# am-1801.net
KiCad netlist of a schematic drawn in EAGLE
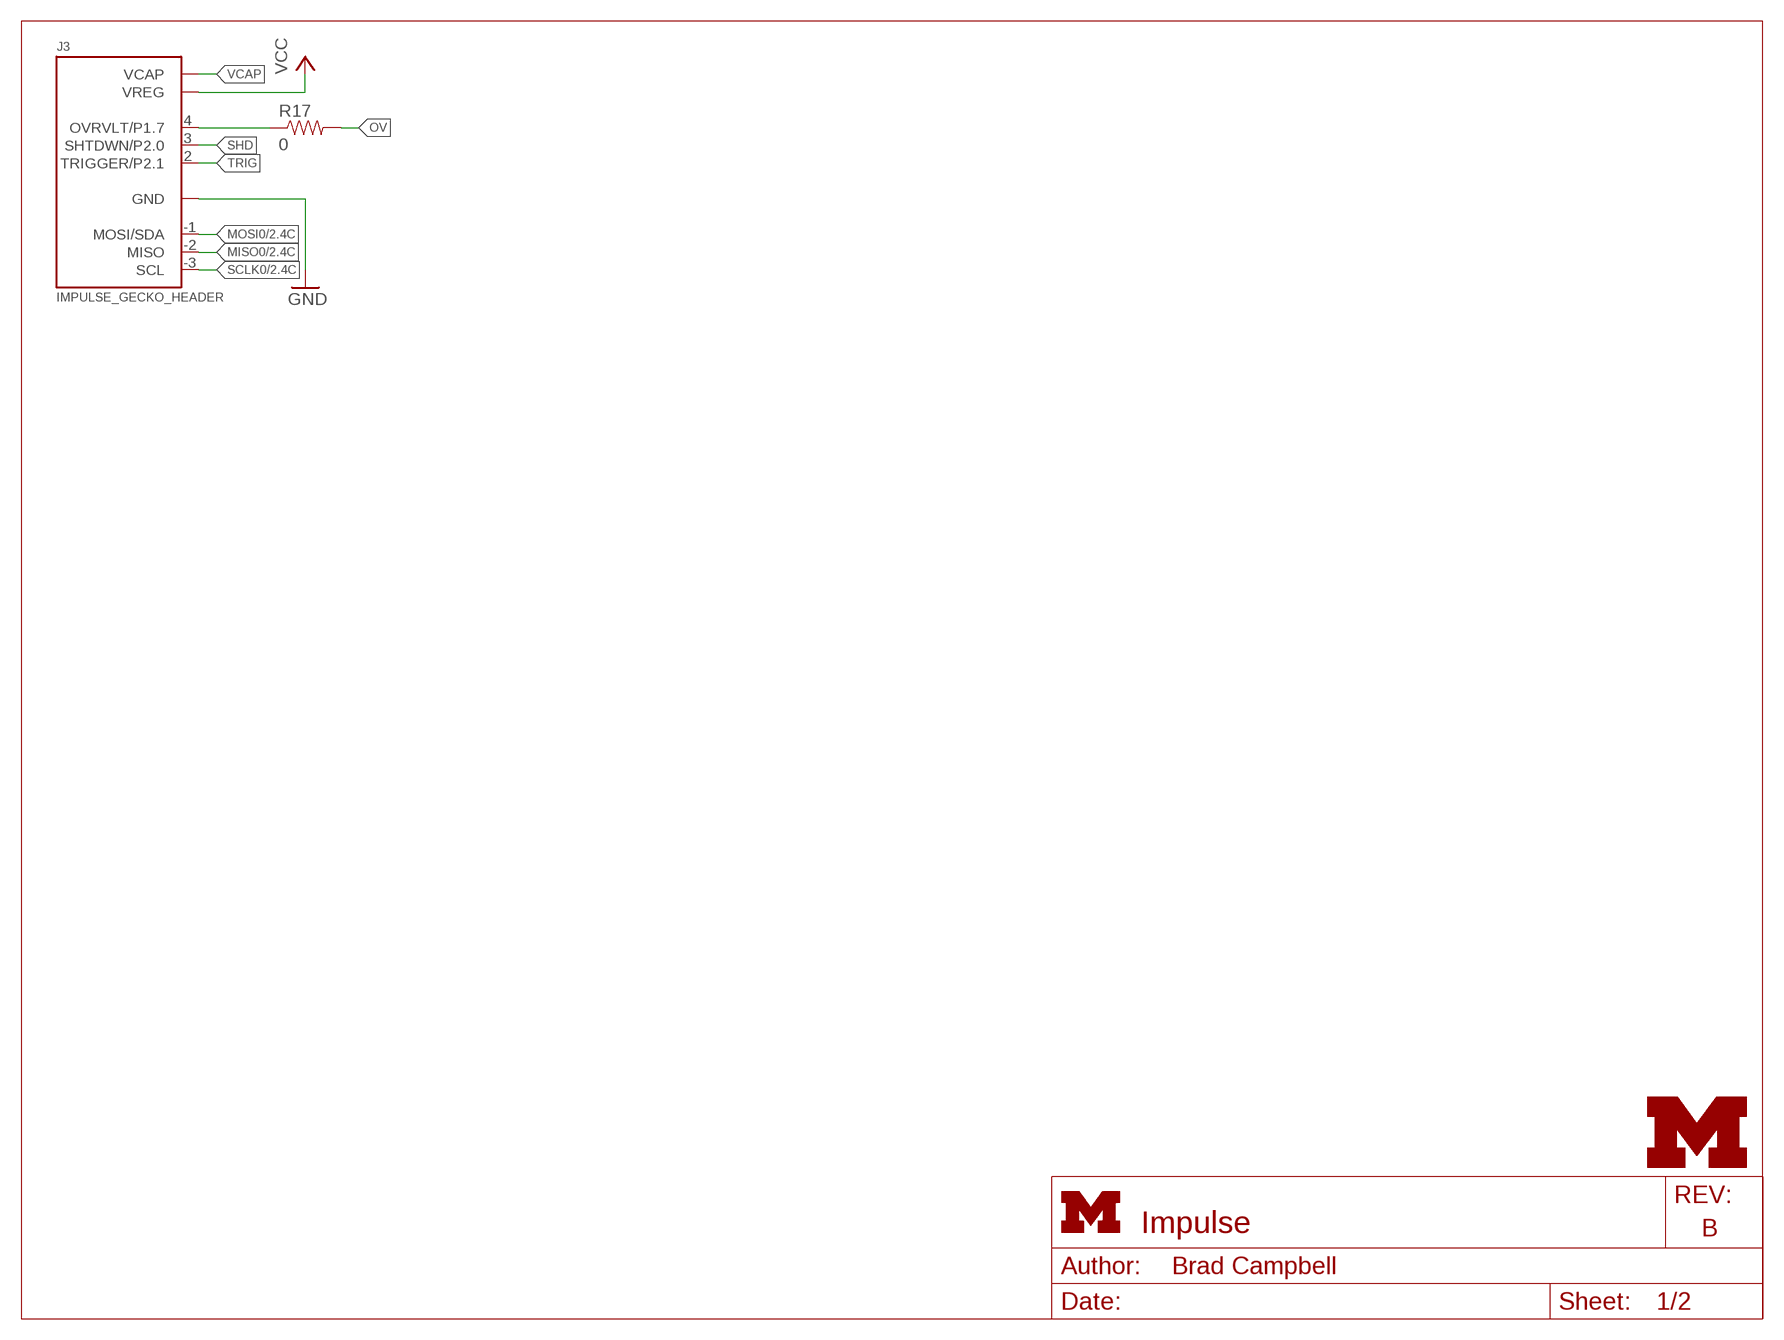
[diagram p0: schematic, sheet 1]
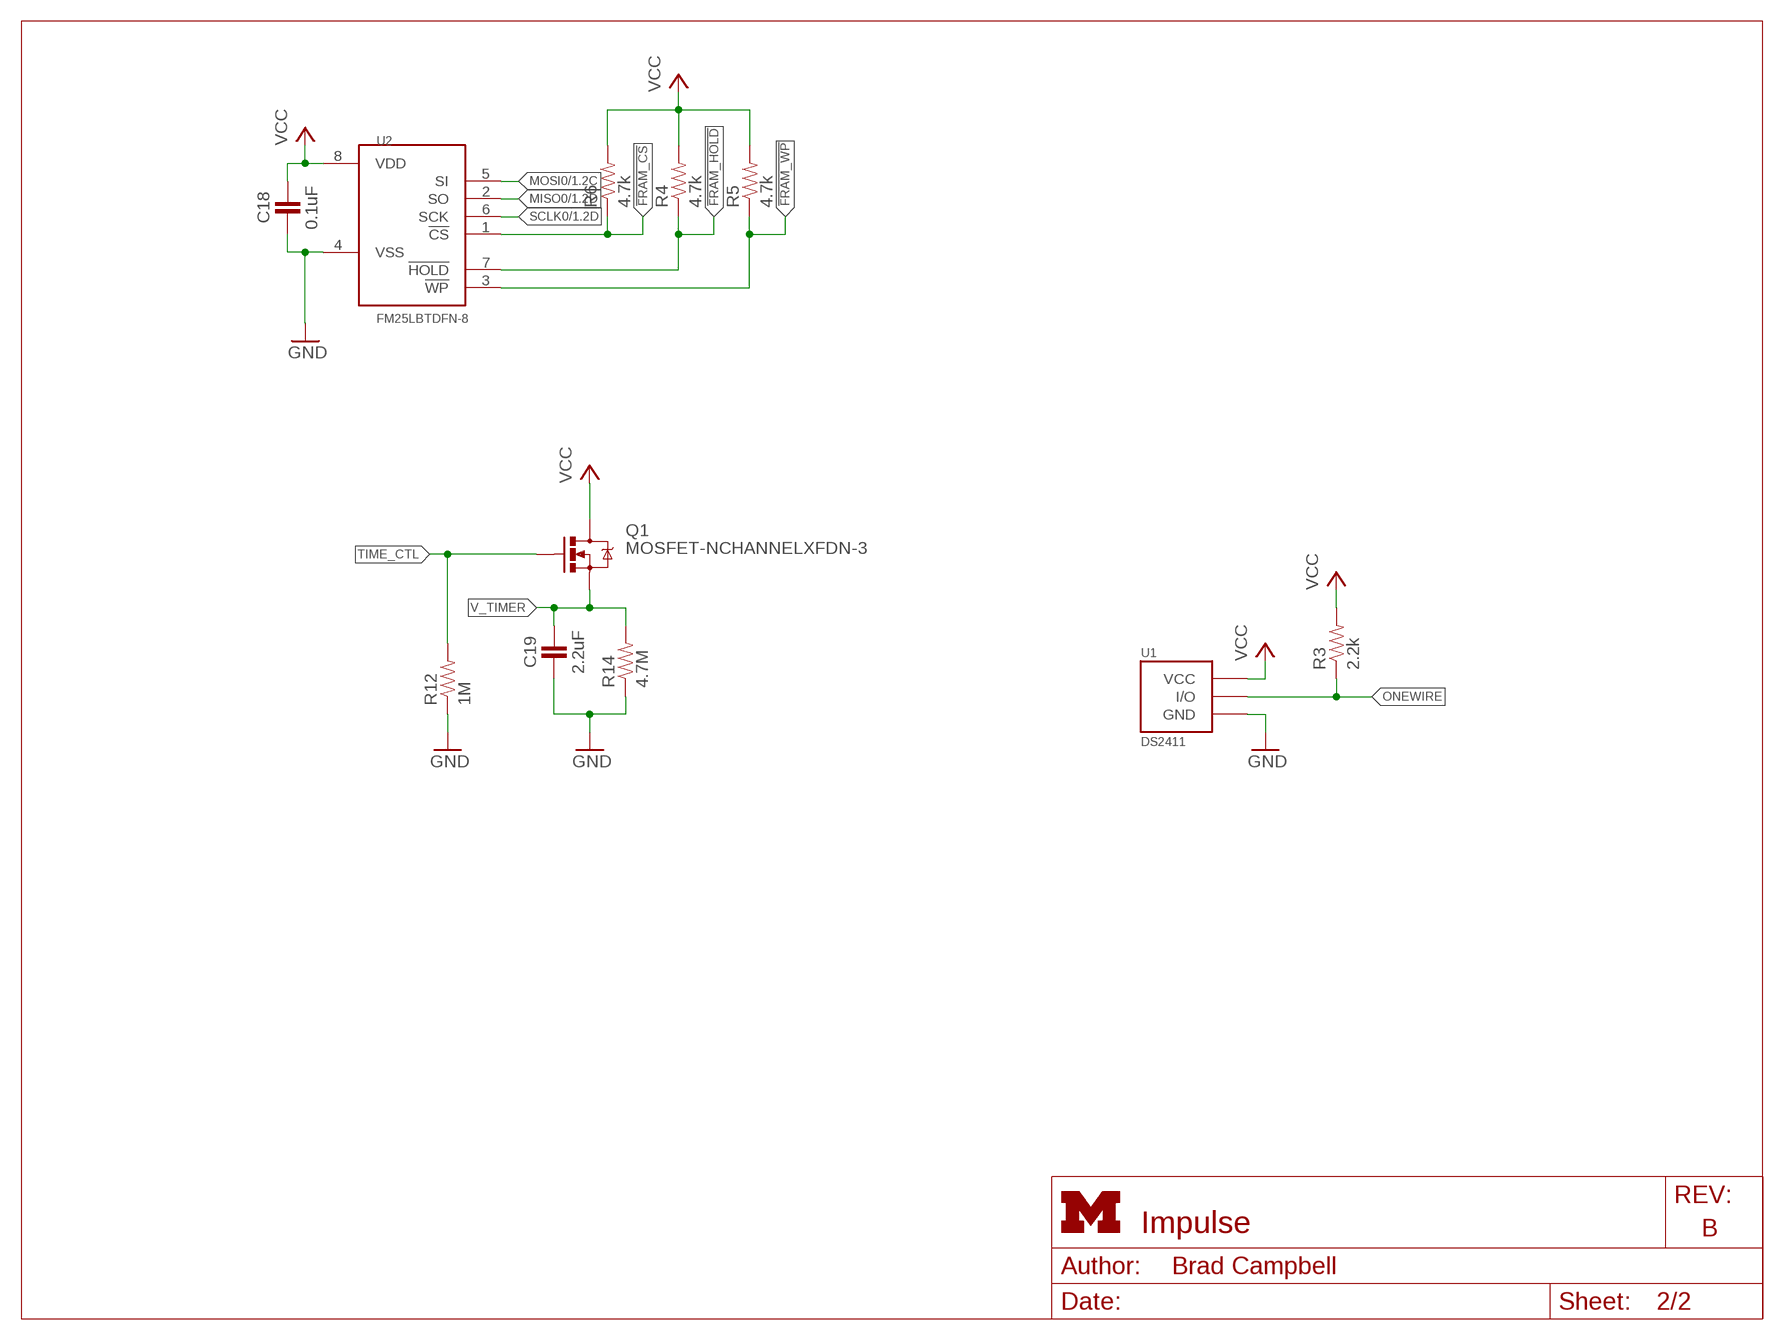
[diagram p1: schematic, sheet 2]

(export (version "E")
  (design (tool "Eeschema 10.0.6"))
  (components
    (comp (ref "C18")
      (value "0.1uF")
      (footprint "eagle-import:0402_CAP")
      (libsource (lib "eagle-import") (part "CAPACITOR"))
    )
    (comp (ref "C19")
      (value "2.2uF")
      (footprint "eagle-import:0402_CAP")
      (libsource (lib "eagle-import") (part "CAPACITOR"))
    )
    (comp (ref "Q1")
      (value "MOSFET-NCHANNELXFDN-3")
      (footprint "eagle-import:XFDFN-3")
      (libsource (lib "eagle-import") (part "MOSFET-NCHANNELXFDN-3"))
    )
    (comp (ref "R3")
      (value "2.2k")
      (footprint "eagle-import:0402_RES")
      (libsource (lib "eagle-import") (part "RESISTOR"))
    )
    (comp (ref "R4")
      (value "4.7k")
      (footprint "eagle-import:0402_RES")
      (libsource (lib "eagle-import") (part "RESISTOR"))
    )
    (comp (ref "R5")
      (value "4.7k")
      (footprint "eagle-import:0402_RES")
      (libsource (lib "eagle-import") (part "RESISTOR"))
    )
    (comp (ref "R6")
      (value "4.7k")
      (footprint "eagle-import:0402_RES")
      (libsource (lib "eagle-import") (part "RESISTOR"))
    )
    (comp (ref "R12")
      (value "1M")
      (footprint "eagle-import:0402_RES")
      (libsource (lib "eagle-import") (part "RESISTOR"))
    )
    (comp (ref "R14")
      (value "4.7M")
      (footprint "eagle-import:0402_RES")
      (libsource (lib "eagle-import") (part "RESISTOR"))
    )
    (comp (ref "U1")
      (value "DS2411")
      (footprint "eagle-import:SOT-23")
      (libsource (lib "eagle-import") (part "DS2411"))
    )
    (comp (ref "U2")
      (value "FM25LBTDFN-8")
      (footprint "eagle-import:TDFN-8")
      (libsource (lib "eagle-import") (part "FM25LBTDFN-8"))
    )
    (comp (ref "J3")
      (value "IMPULSE_GECKO_HEADER")
      (footprint "eagle-import:HEADER1X9_0.05IN")
      (libsource (lib "eagle-import") (part "IMPULSE_GECKO_HEADER"))
    )
    (comp (ref "R17")
      (value "0")
      (footprint "eagle-import:0402_RES")
      (libsource (lib "eagle-import") (part "RESISTOR"))
    )
    (comp (ref "U$1")
      (value "UMICH_SOLID_SMALL")
      (footprint "eagle-import:UMICH_SOLID_75MIL")
      (libsource (lib "eagle-import") (part "UMICH_SOLID_SMALL"))
    )
  )
  (nets
    (net (code "1") (name "GND") (class "Default")
      (node (ref "C18") (pin "2") (pinfunction "2_2") (pintype "bidirectional"))
      (node (ref "C19") (pin "2") (pinfunction "2_2") (pintype "bidirectional"))
      (node (ref "J3") (pin "0") (pinfunction "GND_0") (pintype "bidirectional"))
      (node (ref "R12") (pin "1") (pinfunction "1_1") (pintype "passive"))
      (node (ref "R14") (pin "1") (pinfunction "1_1") (pintype "passive"))
      (node (ref "U1") (pin "3") (pinfunction "GND_3") (pintype "bidirectional"))
      (node (ref "U2") (pin "4") (pinfunction "VSS_4") (pintype "bidirectional"))
    )
    (net (code "2") (name "MISO0") (class "Default")
      (node (ref "J3") (pin "-2") (pinfunction "MISO_-2") (pintype "bidirectional"))
      (node (ref "U2") (pin "2") (pinfunction "SO_2") (pintype "bidirectional"))
    )
    (net (code "3") (name "MOSI0") (class "Default")
      (node (ref "J3") (pin "-1") (pinfunction "MOSI/SDA_-1") (pintype "bidirectional"))
      (node (ref "U2") (pin "5") (pinfunction "SI_5") (pintype "bidirectional"))
    )
    (net (code "4") (name "Net-(J3-OVRVLT{slash}P1.7)") (class "Default")
      (node (ref "J3") (pin "4") (pinfunction "OVRVLT/P1.7_4") (pintype "bidirectional"))
      (node (ref "R17") (pin "1") (pinfunction "1_1") (pintype "passive"))
    )
    (net (code "5") (name "ONEWIRE") (class "Default")
      (node (ref "R3") (pin "1") (pinfunction "1_1") (pintype "passive"))
      (node (ref "U1") (pin "1") (pinfunction "I/O_1") (pintype "bidirectional"))
    )
    (net (code "6") (name "OV") (class "Default")
      (node (ref "R17") (pin "2") (pinfunction "2_2") (pintype "passive"))
    )
    (net (code "7") (name "SCLK0") (class "Default")
      (node (ref "J3") (pin "-3") (pinfunction "SCL_-3") (pintype "bidirectional"))
      (node (ref "U2") (pin "6") (pinfunction "SCK_6") (pintype "bidirectional"))
    )
    (net (code "8") (name "SHD") (class "Default")
      (node (ref "J3") (pin "3") (pinfunction "SHTDWN/P2.0_3") (pintype "bidirectional"))
    )
    (net (code "9") (name "TIME_CTL") (class "Default")
      (node (ref "Q1") (pin "G") (pinfunction "G_G") (pintype "passive"))
      (node (ref "R12") (pin "2") (pinfunction "2_2") (pintype "passive"))
    )
    (net (code "10") (name "TRIG") (class "Default")
      (node (ref "J3") (pin "2") (pinfunction "TRIGGER/P2.1_2") (pintype "bidirectional"))
    )
    (net (code "11") (name "VCAP") (class "Default")
      (node (ref "J3") (pin "5") (pinfunction "VCAP_5") (pintype "output"))
    )
    (net (code "12") (name "VCC") (class "Default")
      (node (ref "C18") (pin "1") (pinfunction "1_1") (pintype "bidirectional"))
      (node (ref "J3") (pin "1") (pinfunction "VREG_1") (pintype "bidirectional"))
      (node (ref "Q1") (pin "D") (pinfunction "D_D") (pintype "passive"))
      (node (ref "R3") (pin "2") (pinfunction "2_2") (pintype "passive"))
      (node (ref "R4") (pin "2") (pinfunction "2_2") (pintype "passive"))
      (node (ref "R5") (pin "2") (pinfunction "2_2") (pintype "passive"))
      (node (ref "R6") (pin "2") (pinfunction "2_2") (pintype "passive"))
      (node (ref "U1") (pin "2") (pinfunction "VCC_2") (pintype "bidirectional"))
      (node (ref "U2") (pin "8") (pinfunction "VDD_8") (pintype "bidirectional"))
    )
    (net (code "13") (name "V_TIMER") (class "Default")
      (node (ref "C19") (pin "1") (pinfunction "1_1") (pintype "bidirectional"))
      (node (ref "Q1") (pin "S") (pinfunction "S_S") (pintype "passive"))
      (node (ref "R14") (pin "2") (pinfunction "2_2") (pintype "passive"))
    )
    (net (code "14") (name "~{FRAM_CS}") (class "Default")
      (node (ref "R6") (pin "1") (pinfunction "1_1") (pintype "passive"))
      (node (ref "U2") (pin "1") (pinfunction "~{CS}_1") (pintype "bidirectional"))
    )
    (net (code "15") (name "~{FRAM_HOLD}") (class "Default")
      (node (ref "R4") (pin "1") (pinfunction "1_1") (pintype "passive"))
      (node (ref "U2") (pin "7") (pinfunction "~{HOLD}_7") (pintype "bidirectional"))
    )
    (net (code "16") (name "~{FRAM_WP}") (class "Default")
      (node (ref "R5") (pin "1") (pinfunction "1_1") (pintype "passive"))
      (node (ref "U2") (pin "3") (pinfunction "~{WP}_3") (pintype "bidirectional"))
    )
  )
)
